# nRF52832_pin_map.net
KiCad netlist of a schematic drawn in Altium Designer
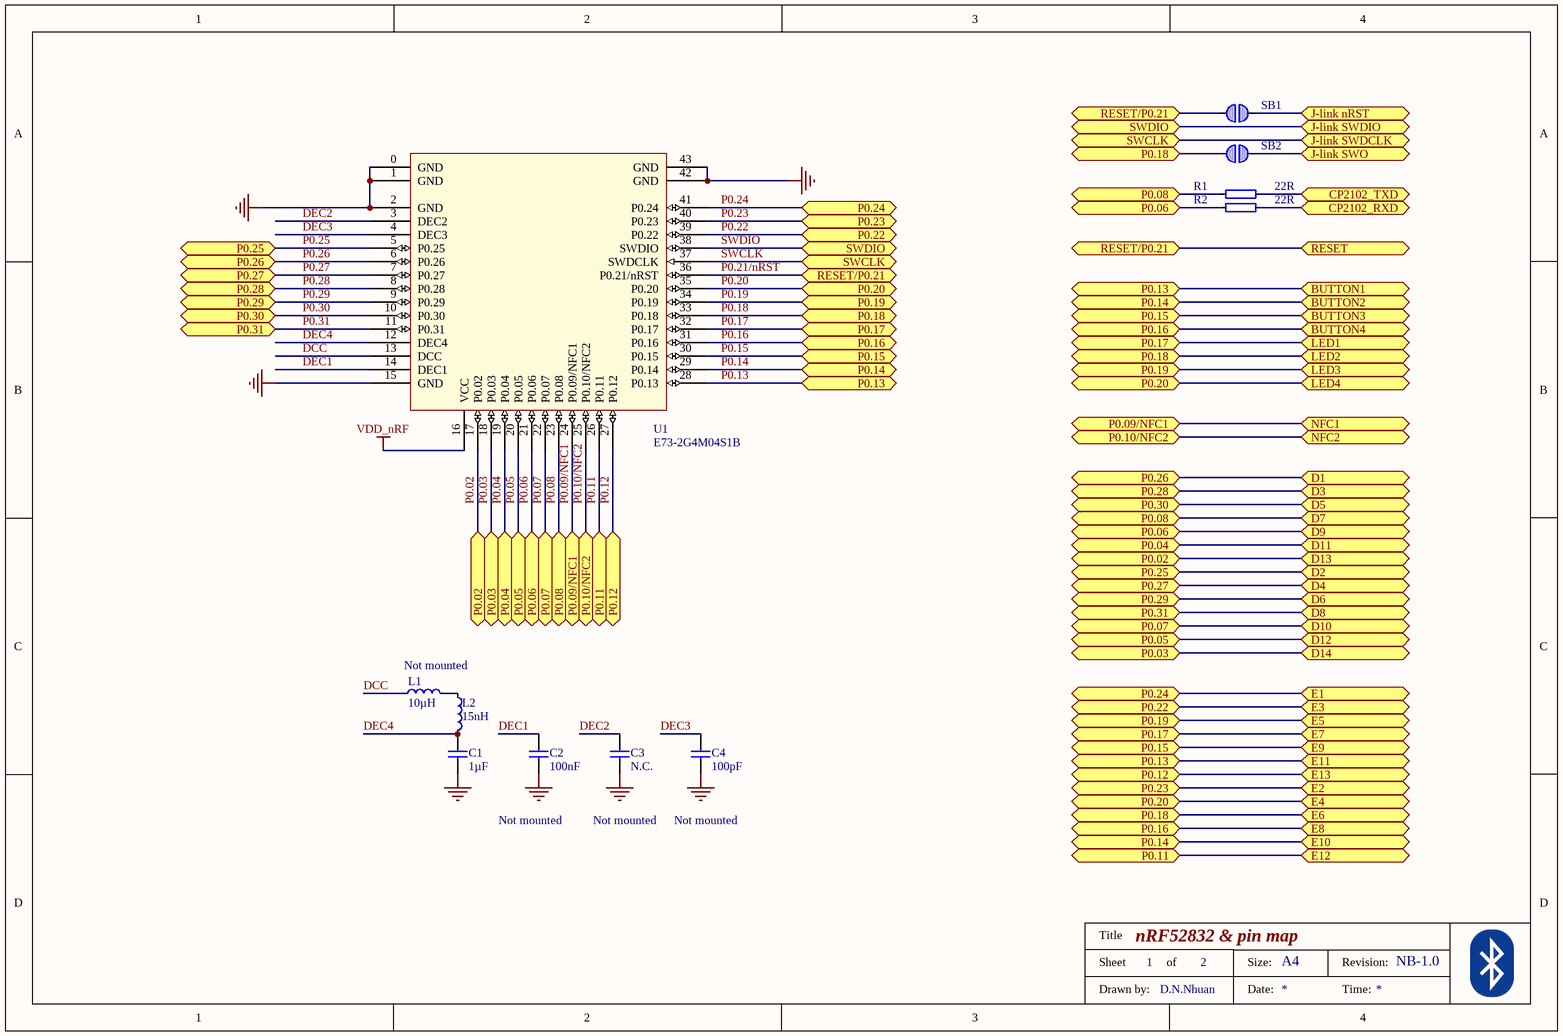
[diagram p0: nRF52832&pin_map.SchDoc]

(export (version "E")
  (design (tool "Eeschema 10.0.6"))
  (components
    (comp (ref "C1")
      (value "1µF")
      (footprint "0603_Imperial")
      (description "common library")
      (fields (field (name "TOLERANCE") "±5%"))
      (libsource (lib "Common_Library") (part "Capacitor"))
    )
    (comp (ref "C2")
      (value "100nF")
      (footprint "0402 imperial")
      (description "common library")
      (fields (field (name "TOLERANCE") "±5%"))
      (libsource (lib "Common_Library") (part "Capacitor"))
    )
    (comp (ref "C3")
      (value "N.C.")
      (footprint "0402 imperial")
      (description "common library")
      (fields (field (name "TOLERANCE") "±5%"))
      (libsource (lib "Common_Library") (part "Capacitor"))
    )
    (comp (ref "C4")
      (value "100pF")
      (footprint "0402 imperial")
      (description "common library")
      (fields (field (name "TOLERANCE") "±5%"))
      (libsource (lib "Common_Library") (part "Capacitor"))
    )
    (comp (ref "L1")
      (value "10µH")
      (footprint "0603_Imperial")
      (description "common library")
      (libsource (lib "Common_Library") (part "Inductor"))
    )
    (comp (ref "L2")
      (value "15nH")
      (footprint "0402 imperial")
      (description "common library")
      (libsource (lib "Common_Library") (part "Inductor"))
    )
    (comp (ref "R1")
      (value "22R")
      (footprint "0402 imperial")
      (description "common library")
      (fields (field (name "TOLERANCE") "±5%"))
      (libsource (lib "Common_Library") (part "Resistor"))
    )
    (comp (ref "R2")
      (value "22R")
      (footprint "0402 imperial")
      (description "common library")
      (fields (field (name "TOLERANCE") "±5%"))
      (libsource (lib "Common_Library") (part "Resistor"))
    )
    (comp (ref "SB1")
      (value "Solderbridge")
      (footprint "Solderbridge")
      (fields (field (name "PUBLISHER") "Nordic Semiconductor"))
      (libsource (lib "Common_Library") (part "Solderbridge"))
    )
    (comp (ref "SB2")
      (value "Solderbridge")
      (footprint "Solderbridge")
      (fields (field (name "PUBLISHER") "Nordic Semiconductor"))
      (libsource (lib "Common_Library") (part "Solderbridge"))
    )
    (comp (ref "U1")
      (value "E73-2G4M04S1B")
      (footprint "nRF52832-Ebyte")
      (description "Ebyte E73-2G4M04S-52832")
      (fields (field (name "MANUFACTURER") "EBYTE"))
      (libsource (lib "MCU_Library") (part "nRF52832-Ebyte"))
    )
  )
  (nets
    (net (code "1") (name "/CP2102_RXD") (class "Default")
      (node (ref "R2") (pin "2") (pinfunction "2_2") (pintype "passive"))
    )
    (net (code "2") (name "/CP2102_TXD") (class "Default")
      (node (ref "R1") (pin "2") (pinfunction "2_2") (pintype "passive"))
    )
    (net (code "3") (name "/DCC") (class "Default")
      (node (ref "L1") (pin "1") (pinfunction "1_1") (pintype "passive"))
      (node (ref "U1") (pin "13") (pinfunction "DCC_13") (pintype "passive"))
    )
    (net (code "4") (name "/DEC1") (class "Default")
      (node (ref "C2") (pin "2") (pinfunction "2_2") (pintype "passive"))
      (node (ref "U1") (pin "14") (pinfunction "DEC1_14") (pintype "passive"))
    )
    (net (code "5") (name "/DEC2") (class "Default")
      (node (ref "C3") (pin "2") (pinfunction "2_2") (pintype "passive"))
      (node (ref "U1") (pin "3") (pinfunction "DEC2_3") (pintype "passive"))
    )
    (net (code "6") (name "/DEC3") (class "Default")
      (node (ref "C4") (pin "2") (pinfunction "2_2") (pintype "passive"))
      (node (ref "U1") (pin "4") (pinfunction "DEC3_4") (pintype "passive"))
    )
    (net (code "7") (name "/DEC4") (class "Default")
      (node (ref "C1") (pin "2") (pinfunction "2_2") (pintype "passive"))
      (node (ref "L2") (pin "2") (pinfunction "2_2") (pintype "passive"))
      (node (ref "U1") (pin "12") (pinfunction "DEC4_12") (pintype "passive"))
    )
    (net (code "8") (name "/J-link SWO") (class "Default")
      (node (ref "SB2") (pin "1") (pinfunction "0_1") (pintype "passive"))
    )
    (net (code "9") (name "/J-link nRST") (class "Default")
      (node (ref "SB1") (pin "1") (pinfunction "0_1") (pintype "passive"))
    )
    (net (code "10") (name "/P0.02") (class "Default")
      (node (ref "U1") (pin "17") (pinfunction "P0.02_17") (pintype "bidirectional"))
    )
    (net (code "11") (name "/P0.03") (class "Default")
      (node (ref "U1") (pin "18") (pinfunction "P0.03_18") (pintype "bidirectional"))
    )
    (net (code "12") (name "/P0.04") (class "Default")
      (node (ref "U1") (pin "19") (pinfunction "P0.04_19") (pintype "bidirectional"))
    )
    (net (code "13") (name "/P0.05") (class "Default")
      (node (ref "U1") (pin "20") (pinfunction "P0.05_20") (pintype "bidirectional"))
    )
    (net (code "14") (name "/P0.06") (class "Default")
      (node (ref "R2") (pin "1") (pinfunction "1_1") (pintype "passive"))
      (node (ref "U1") (pin "21") (pinfunction "P0.06_21") (pintype "bidirectional"))
    )
    (net (code "15") (name "/P0.07") (class "Default")
      (node (ref "U1") (pin "22") (pinfunction "P0.07_22") (pintype "bidirectional"))
    )
    (net (code "16") (name "/P0.08") (class "Default")
      (node (ref "R1") (pin "1") (pinfunction "1_1") (pintype "passive"))
      (node (ref "U1") (pin "23") (pinfunction "P0.08_23") (pintype "bidirectional"))
    )
    (net (code "17") (name "/P0.09{slash}NFC1") (class "Default")
      (node (ref "U1") (pin "24") (pinfunction "P0.09/NFC1_24") (pintype "bidirectional"))
    )
    (net (code "18") (name "/P0.10{slash}NFC2") (class "Default")
      (node (ref "U1") (pin "25") (pinfunction "P0.10/NFC2_25") (pintype "bidirectional"))
    )
    (net (code "19") (name "/P0.11") (class "Default")
      (node (ref "U1") (pin "26") (pinfunction "P0.11_26") (pintype "bidirectional"))
    )
    (net (code "20") (name "/P0.12") (class "Default")
      (node (ref "U1") (pin "27") (pinfunction "P0.12_27") (pintype "bidirectional"))
    )
    (net (code "21") (name "/P0.13") (class "Default")
      (node (ref "U1") (pin "28") (pinfunction "P0.13_28") (pintype "bidirectional"))
    )
    (net (code "22") (name "/P0.14") (class "Default")
      (node (ref "U1") (pin "29") (pinfunction "P0.14_29") (pintype "bidirectional"))
    )
    (net (code "23") (name "/P0.15") (class "Default")
      (node (ref "U1") (pin "30") (pinfunction "P0.15_30") (pintype "bidirectional"))
    )
    (net (code "24") (name "/P0.16") (class "Default")
      (node (ref "U1") (pin "31") (pinfunction "P0.16_31") (pintype "bidirectional"))
    )
    (net (code "25") (name "/P0.17") (class "Default")
      (node (ref "U1") (pin "32") (pinfunction "P0.17_32") (pintype "bidirectional"))
    )
    (net (code "26") (name "/P0.18") (class "Default")
      (node (ref "SB2") (pin "2") (pinfunction "1_2") (pintype "passive"))
      (node (ref "U1") (pin "33") (pinfunction "P0.18_33") (pintype "bidirectional"))
    )
    (net (code "27") (name "/P0.19") (class "Default")
      (node (ref "U1") (pin "34") (pinfunction "P0.19_34") (pintype "bidirectional"))
    )
    (net (code "28") (name "/P0.20") (class "Default")
      (node (ref "U1") (pin "35") (pinfunction "P0.20_35") (pintype "bidirectional"))
    )
    (net (code "29") (name "/P0.21{slash}nRST") (class "Default")
      (node (ref "SB1") (pin "2") (pinfunction "1_2") (pintype "passive"))
      (node (ref "U1") (pin "36") (pinfunction "P0.21/nRST_36") (pintype "bidirectional"))
    )
    (net (code "30") (name "/P0.22") (class "Default")
      (node (ref "U1") (pin "39") (pinfunction "P0.22_39") (pintype "bidirectional"))
    )
    (net (code "31") (name "/P0.23") (class "Default")
      (node (ref "U1") (pin "40") (pinfunction "P0.23_40") (pintype "bidirectional"))
    )
    (net (code "32") (name "/P0.24") (class "Default")
      (node (ref "U1") (pin "41") (pinfunction "P0.24_41") (pintype "bidirectional"))
    )
    (net (code "33") (name "/P0.25") (class "Default")
      (node (ref "U1") (pin "5") (pinfunction "P0.25_5") (pintype "bidirectional"))
    )
    (net (code "34") (name "/P0.26") (class "Default")
      (node (ref "U1") (pin "6") (pinfunction "P0.26_6") (pintype "bidirectional"))
    )
    (net (code "35") (name "/P0.27") (class "Default")
      (node (ref "U1") (pin "7") (pinfunction "P0.27_7") (pintype "bidirectional"))
    )
    (net (code "36") (name "/P0.28") (class "Default")
      (node (ref "U1") (pin "8") (pinfunction "P0.28_8") (pintype "bidirectional"))
    )
    (net (code "37") (name "/P0.29") (class "Default")
      (node (ref "U1") (pin "9") (pinfunction "P0.29_9") (pintype "bidirectional"))
    )
    (net (code "38") (name "/P0.30") (class "Default")
      (node (ref "U1") (pin "10") (pinfunction "P0.30_10") (pintype "bidirectional"))
    )
    (net (code "39") (name "/P0.31") (class "Default")
      (node (ref "U1") (pin "11") (pinfunction "P0.31_11") (pintype "bidirectional"))
    )
    (net (code "40") (name "/SWCLK") (class "Default")
      (node (ref "U1") (pin "37") (pinfunction "SWDCLK_37") (pintype "input"))
    )
    (net (code "41") (name "/SWDIO") (class "Default")
      (node (ref "U1") (pin "38") (pinfunction "SWDIO_38") (pintype "bidirectional"))
    )
    (net (code "42") (name "GND") (class "Default")
      (node (ref "C1") (pin "1") (pinfunction "1_1") (pintype "passive"))
      (node (ref "C2") (pin "1") (pinfunction "1_1") (pintype "passive"))
      (node (ref "C3") (pin "1") (pinfunction "1_1") (pintype "passive"))
      (node (ref "C4") (pin "1") (pinfunction "1_1") (pintype "passive"))
      (node (ref "U1") (pin "0") (pinfunction "GND_0") (pintype "power_in"))
      (node (ref "U1") (pin "1") (pinfunction "GND_1") (pintype "power_in"))
      (node (ref "U1") (pin "15") (pinfunction "GND_15") (pintype "power_in"))
      (node (ref "U1") (pin "2") (pinfunction "GND_2") (pintype "power_in"))
      (node (ref "U1") (pin "42") (pinfunction "GND_42") (pintype "power_in"))
      (node (ref "U1") (pin "43") (pinfunction "GND_43") (pintype "power_in"))
    )
    (net (code "43") (name "Net-(L1-Pad2)") (class "Default")
      (node (ref "L1") (pin "2") (pinfunction "2_2") (pintype "passive"))
      (node (ref "L2") (pin "1") (pinfunction "1_1") (pintype "passive"))
    )
    (net (code "44") (name "VDD_nRF") (class "Default")
      (node (ref "U1") (pin "16") (pinfunction "VCC_16") (pintype "power_in"))
    )
  )
)
